# P09-USB_JTAG.net
KiCad netlist of a schematic drawn in Altium Designer
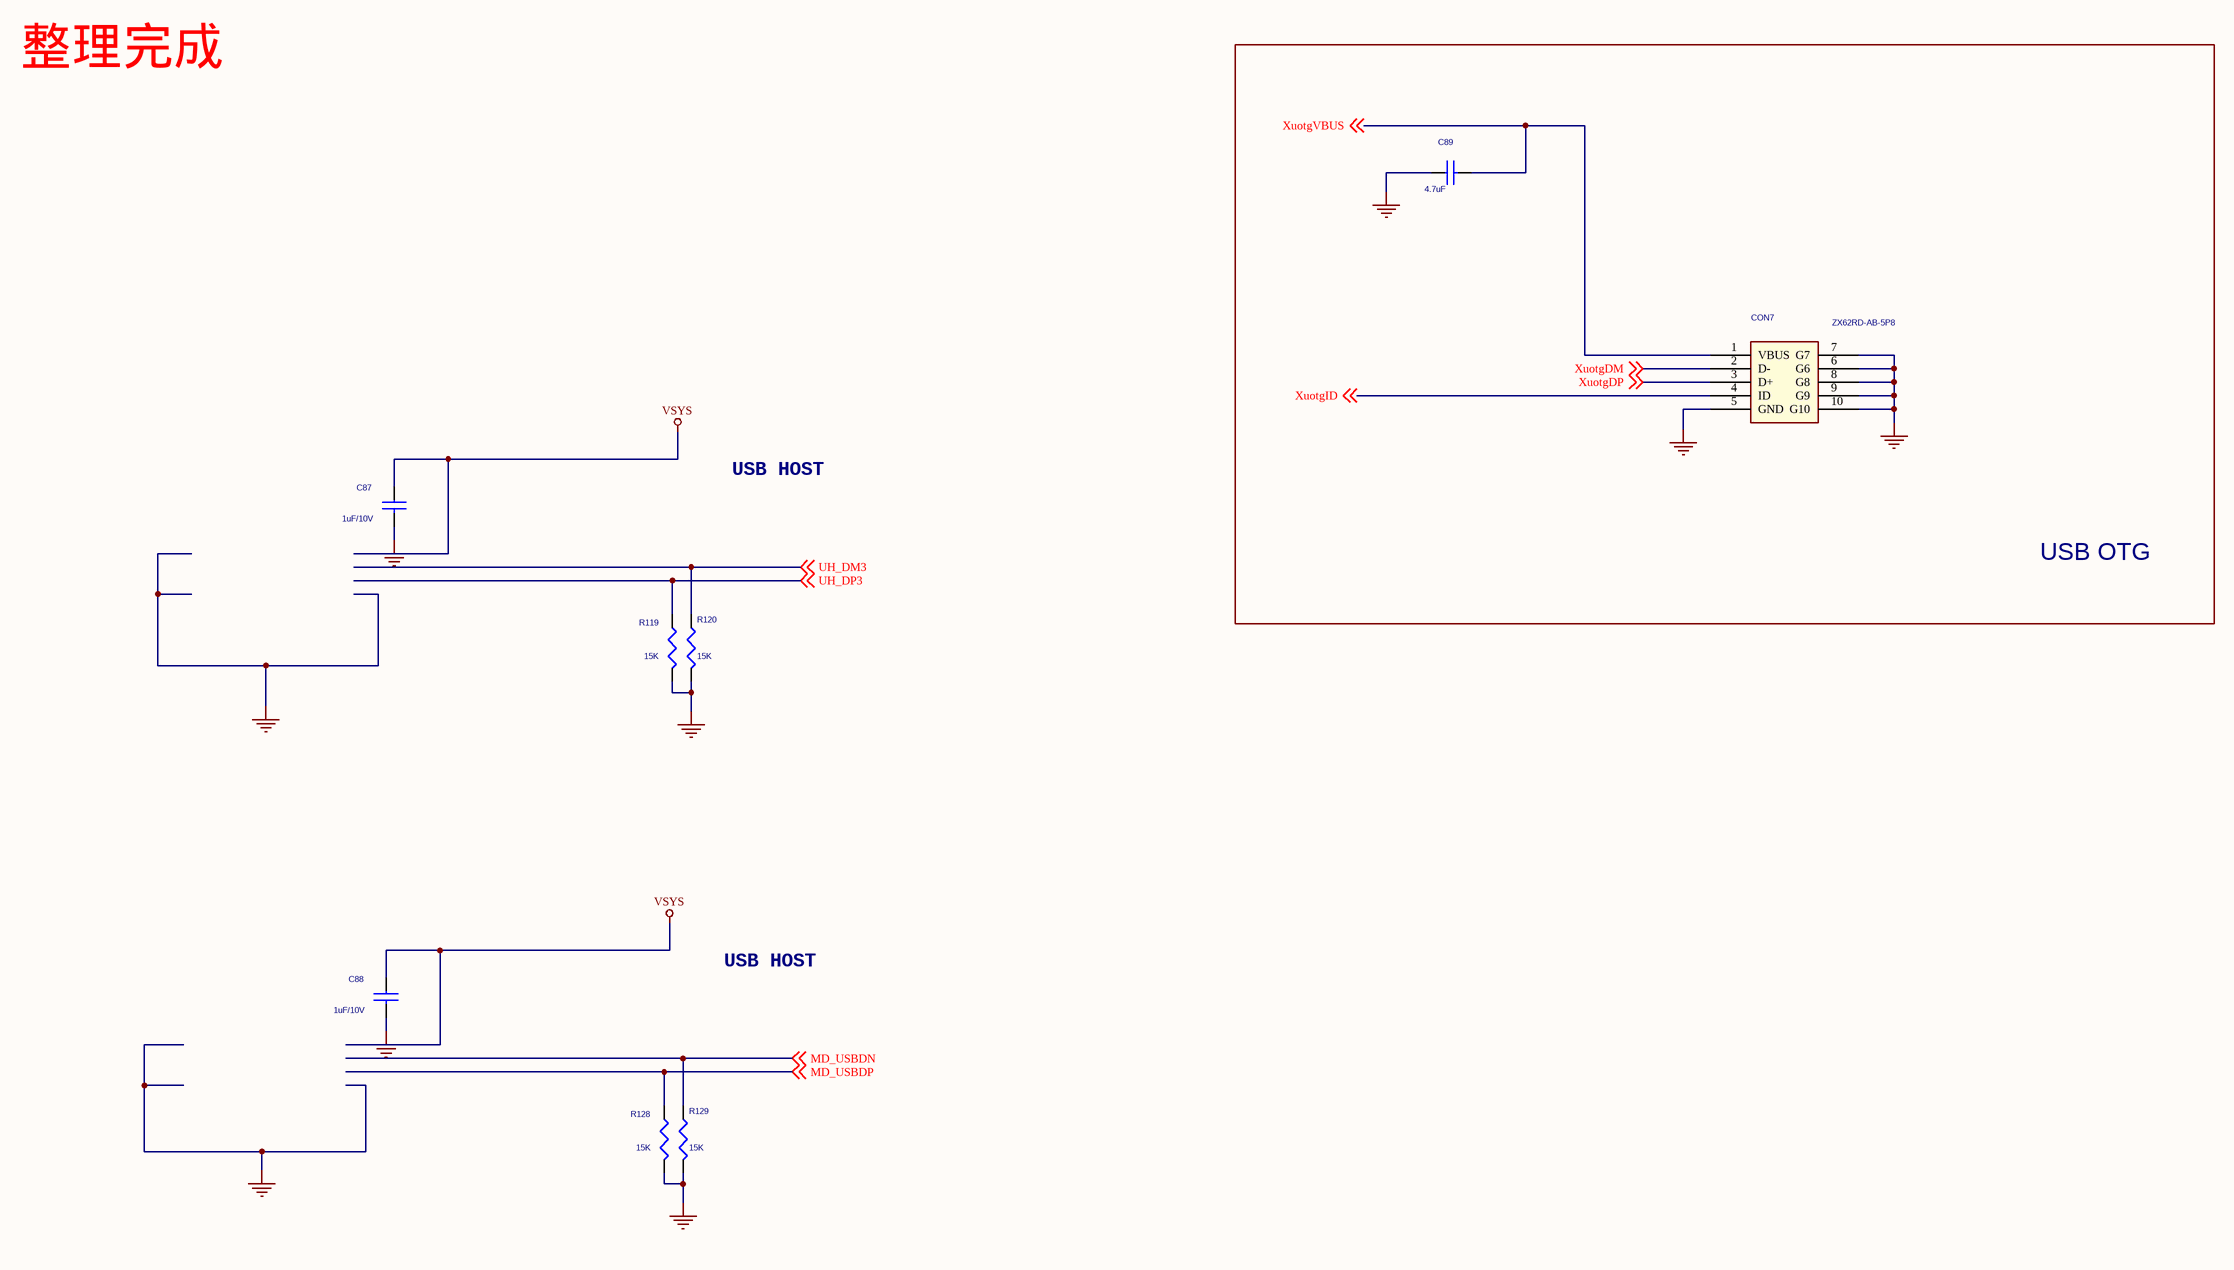
[diagram p0: P09-USB_JTAG.SchDoc]

(export (version "E")
  (design (tool "Eeschema 10.0.6"))
  (components
    (comp (ref "C87") (value "1uF/10V") (footprint "C0603-S") (libsource (lib "*") (part "C0603_0")))
    (comp (ref "C88") (value "1uF/10V") (footprint "C0603-S") (libsource (lib "*") (part "C0603_0")))
    (comp (ref "C89") (value "4.7uF") (footprint "C0603-S") (libsource (lib "*") (part "C1005")))
    (comp (ref "CON7") (value "ZX62RD-AB-5P8") (libsource (lib "*") (part "ZX62RD-AB-5P8_3")))
    (comp (ref "R119") (value "15K") (footprint "R0603-S") (libsource (lib "*") (part "R1005_0")))
    (comp (ref "R120") (value "15K") (footprint "R0603-S") (libsource (lib "*") (part "R1005_0")))
    (comp (ref "R128") (value "15K") (footprint "R0603-S") (libsource (lib "*") (part "R1005_0")))
    (comp (ref "R129") (value "15K") (footprint "R0603-S") (libsource (lib "*") (part "R1005_0")))
  )
  (nets
    (net (code "1") (name "GND") (class "Default")
      (node (ref "C87") (pin "2") (pinfunction "2_2") (pintype "passive"))
      (node (ref "C88") (pin "2") (pinfunction "2_2") (pintype "passive"))
      (node (ref "C89") (pin "1") (pinfunction "1_1") (pintype "passive"))
      (node (ref "CON7") (pin "10") (pinfunction "G10_10") (pintype "passive"))
      (node (ref "CON7") (pin "5") (pinfunction "GND_5") (pintype "passive"))
      (node (ref "CON7") (pin "6") (pinfunction "G6_6") (pintype "passive"))
      (node (ref "CON7") (pin "7") (pinfunction "G7_7") (pintype "passive"))
      (node (ref "CON7") (pin "8") (pinfunction "G8_8") (pintype "passive"))
      (node (ref "CON7") (pin "9") (pinfunction "G9_9") (pintype "passive"))
      (node (ref "R119") (pin "1") (pinfunction "1_1") (pintype "passive"))
      (node (ref "R120") (pin "1") (pinfunction "1_1") (pintype "passive"))
      (node (ref "R128") (pin "1") (pinfunction "1_1") (pintype "passive"))
      (node (ref "R129") (pin "1") (pinfunction "1_1") (pintype "passive"))
    )
    (net (code "2") (name "MD_USBDN") (class "Default")
      (node (ref "R129") (pin "2") (pinfunction "2_2") (pintype "passive"))
    )
    (net (code "3") (name "MD_USBDP") (class "Default")
      (node (ref "R128") (pin "2") (pinfunction "2_2") (pintype "passive"))
    )
    (net (code "4") (name "UH_DM3") (class "Default")
      (node (ref "R120") (pin "2") (pinfunction "2_2") (pintype "passive"))
    )
    (net (code "5") (name "UH_DP3") (class "Default")
      (node (ref "R119") (pin "2") (pinfunction "2_2") (pintype "passive"))
    )
    (net (code "6") (name "VSYS") (class "Default")
      (node (ref "C87") (pin "1") (pinfunction "1_1") (pintype "passive"))
      (node (ref "C88") (pin "1") (pinfunction "1_1") (pintype "passive"))
    )
    (net (code "7") (name "XuotgDM") (class "Default")
      (node (ref "CON7") (pin "2") (pinfunction "D-_2") (pintype "passive"))
    )
    (net (code "8") (name "XuotgDP") (class "Default")
      (node (ref "CON7") (pin "3") (pinfunction "D+_3") (pintype "passive"))
    )
    (net (code "9") (name "XuotgID") (class "Default")
      (node (ref "CON7") (pin "4") (pinfunction "ID_4") (pintype "passive"))
    )
    (net (code "10") (name "XuotgVBUS") (class "Default")
      (node (ref "C89") (pin "2") (pinfunction "2_2") (pintype "passive"))
      (node (ref "CON7") (pin "1") (pinfunction "VBUS_1") (pintype "passive"))
    )
  )
)
